# hijack_jtag_b.net
KiCad netlist of a schematic drawn in EAGLE
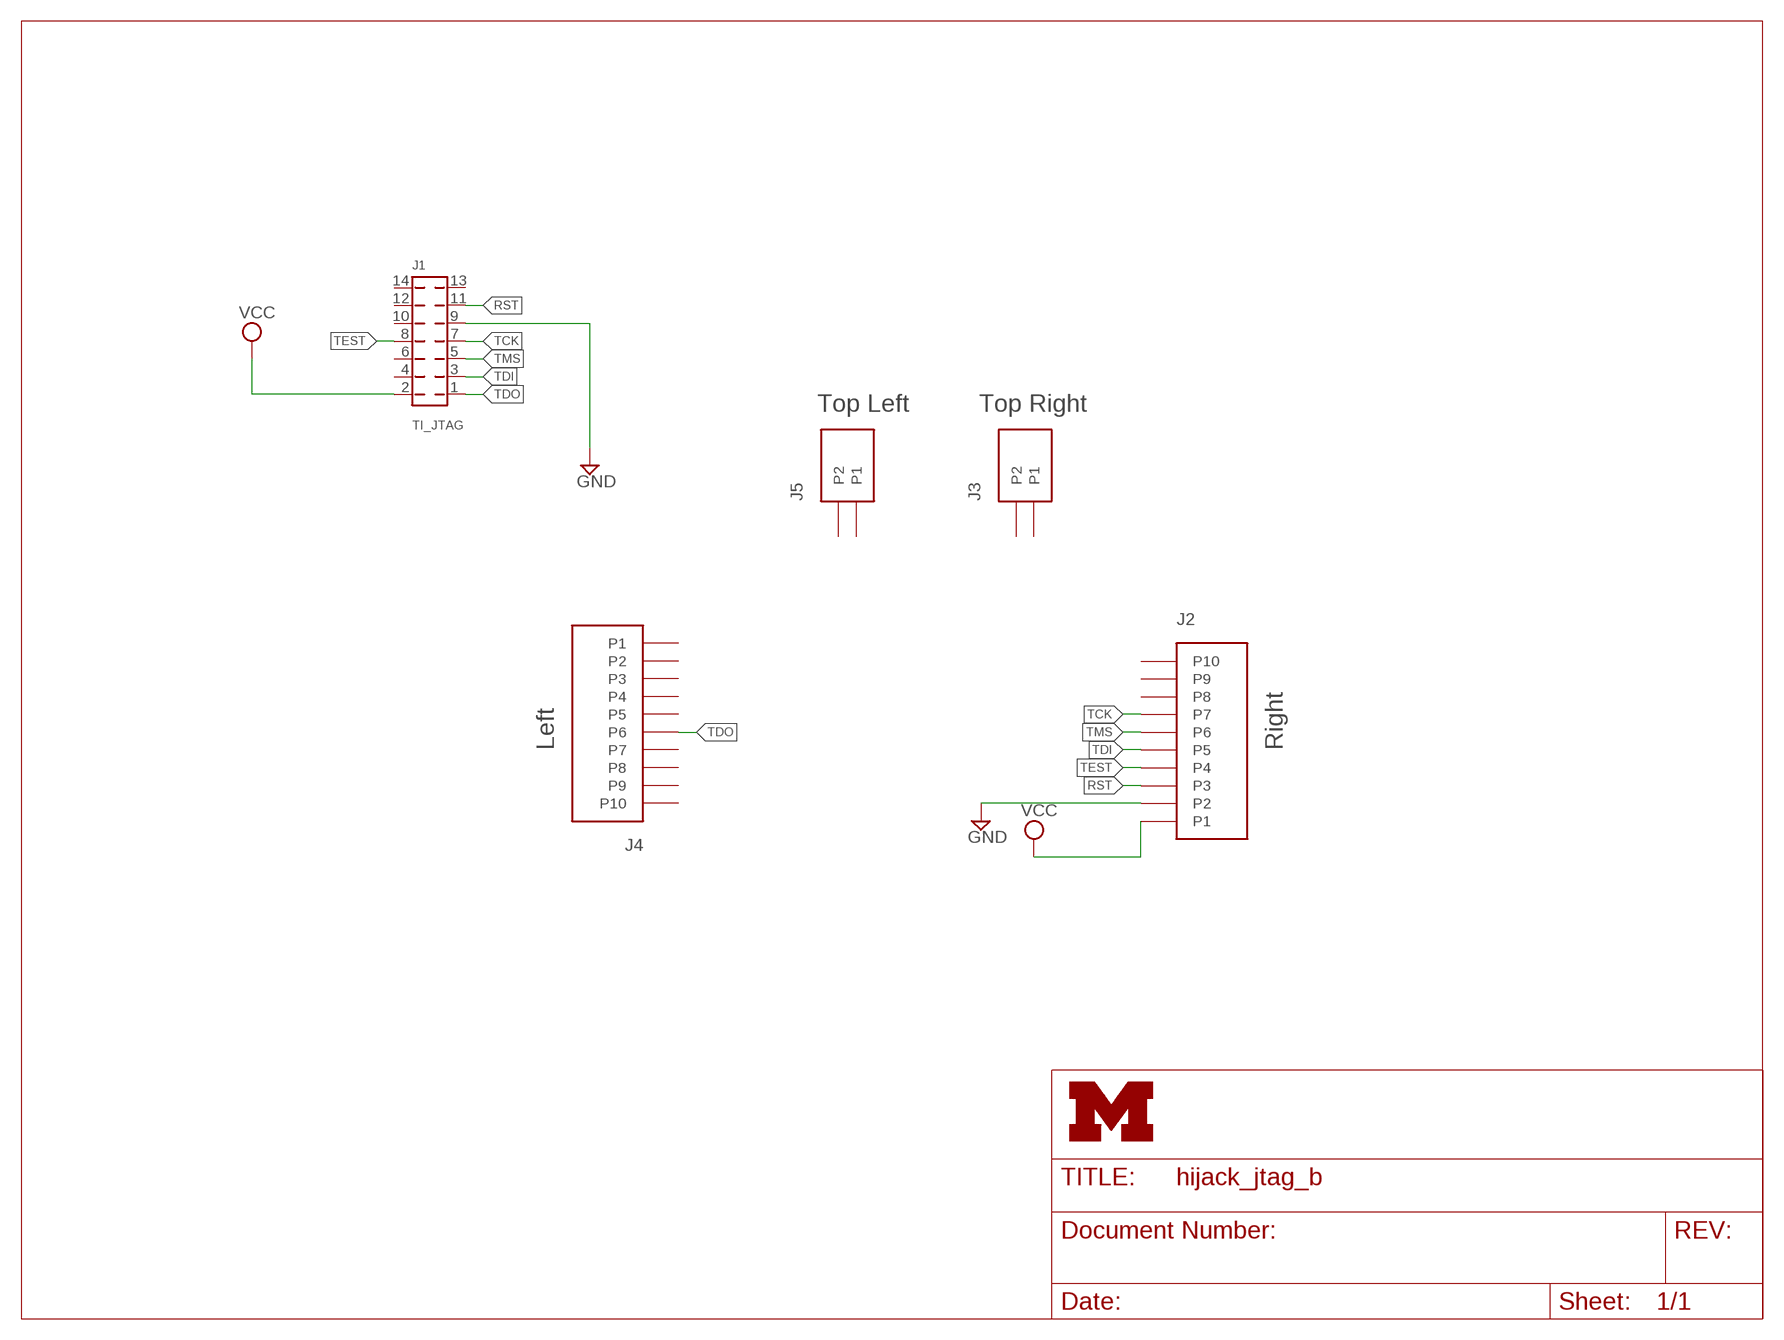
[diagram p0: schematic, sheet 1]

(export (version "E")
  (design (tool "Eeschema 10.0.6"))
  (components
    (comp (ref "J1")
      (value "TI_JTAG")
      (footprint "eagle-import:TST-107")
      (libsource (lib "eagle-import") (part "TI_JTAG"))
    )
    (comp (ref "J2")
      (value "HEADER10POS")
      (footprint "eagle-import:10PIN2MMHEADER")
      (libsource (lib "eagle-import") (part "HEADER10POS"))
    )
    (comp (ref "J3")
      (value "HEADER2POS")
      (footprint "eagle-import:2PIN2MMHEADER")
      (libsource (lib "eagle-import") (part "HEADER2POS"))
    )
    (comp (ref "J4")
      (value "HEADER10POS")
      (footprint "eagle-import:10PIN2MMHEADER")
      (libsource (lib "eagle-import") (part "HEADER10POS"))
    )
    (comp (ref "J5")
      (value "HEADER2POS")
      (footprint "eagle-import:2PIN2MMHEADER")
      (libsource (lib "eagle-import") (part "HEADER2POS"))
    )
    (comp (ref "U$2")
      (value "UMICH_SOLID")
      (footprint "eagle-import:UMICH_SOLID")
      (libsource (lib "eagle-import") (part "UMICH_SOLID"))
    )
  )
  (nets
    (net (code "1") (name "GND") (class "Default")
      (node (ref "J1") (pin "9") (pinfunction "P$9_9") (pintype "bidirectional"))
      (node (ref "J2") (pin "P2") (pinfunction "P2_P2") (pintype "bidirectional"))
    )
    (net (code "2") (name "RST") (class "Default")
      (node (ref "J1") (pin "11") (pinfunction "P$11_11") (pintype "bidirectional"))
      (node (ref "J2") (pin "P3") (pinfunction "P3_P3") (pintype "bidirectional"))
    )
    (net (code "3") (name "TCK") (class "Default")
      (node (ref "J1") (pin "7") (pinfunction "P$7_7") (pintype "bidirectional"))
      (node (ref "J2") (pin "P7") (pinfunction "P7_P7") (pintype "bidirectional"))
    )
    (net (code "4") (name "TDI") (class "Default")
      (node (ref "J1") (pin "3") (pinfunction "P$3_3") (pintype "bidirectional"))
      (node (ref "J2") (pin "P5") (pinfunction "P5_P5") (pintype "bidirectional"))
    )
    (net (code "5") (name "TDO") (class "Default")
      (node (ref "J1") (pin "1") (pinfunction "P$1_1") (pintype "bidirectional"))
      (node (ref "J4") (pin "P6") (pinfunction "P6_P6") (pintype "bidirectional"))
    )
    (net (code "6") (name "TEST") (class "Default")
      (node (ref "J1") (pin "8") (pinfunction "P$8_8") (pintype "bidirectional"))
      (node (ref "J2") (pin "P4") (pinfunction "P4_P4") (pintype "bidirectional"))
    )
    (net (code "7") (name "TMS") (class "Default")
      (node (ref "J1") (pin "5") (pinfunction "P$5_5") (pintype "bidirectional"))
      (node (ref "J2") (pin "P6") (pinfunction "P6_P6") (pintype "bidirectional"))
    )
    (net (code "8") (name "VCC") (class "Default")
      (node (ref "J1") (pin "2") (pinfunction "P$2_2") (pintype "bidirectional"))
      (node (ref "J2") (pin "P1") (pinfunction "P1_P1") (pintype "bidirectional"))
    )
    (net (code "9") (name "unconnected-(J1-P$4-Pad4)") (class "Default")
      (node (ref "J1") (pin "4") (pinfunction "P$4_4") (pintype "bidirectional"))
    )
    (net (code "10") (name "unconnected-(J1-P$6-Pad6)") (class "Default")
      (node (ref "J1") (pin "6") (pinfunction "P$6_6") (pintype "bidirectional"))
    )
    (net (code "11") (name "unconnected-(J1-P$10-Pad10)") (class "Default")
      (node (ref "J1") (pin "10") (pinfunction "P$10_10") (pintype "bidirectional"))
    )
    (net (code "12") (name "unconnected-(J1-P$12-Pad12)") (class "Default")
      (node (ref "J1") (pin "12") (pinfunction "P$12_12") (pintype "bidirectional"))
    )
    (net (code "13") (name "unconnected-(J1-P$13-Pad13)") (class "Default")
      (node (ref "J1") (pin "13") (pinfunction "P$13_13") (pintype "bidirectional"))
    )
    (net (code "14") (name "unconnected-(J1-P$14-Pad14)") (class "Default")
      (node (ref "J1") (pin "14") (pinfunction "P$14_14") (pintype "bidirectional"))
    )
    (net (code "15") (name "unconnected-(J2-PadP8)") (class "Default")
      (node (ref "J2") (pin "P8") (pinfunction "P8_P8") (pintype "bidirectional"))
    )
    (net (code "16") (name "unconnected-(J2-PadP9)") (class "Default")
      (node (ref "J2") (pin "P9") (pinfunction "P9_P9") (pintype "bidirectional"))
    )
    (net (code "17") (name "unconnected-(J2-PadP10)") (class "Default")
      (node (ref "J2") (pin "P10") (pinfunction "P10_P10") (pintype "bidirectional"))
    )
    (net (code "18") (name "unconnected-(J3-PadP1)") (class "Default")
      (node (ref "J3") (pin "P1") (pinfunction "P1_P1") (pintype "bidirectional"))
    )
    (net (code "19") (name "unconnected-(J3-PadP2)") (class "Default")
      (node (ref "J3") (pin "P2") (pinfunction "P2_P2") (pintype "bidirectional"))
    )
    (net (code "20") (name "unconnected-(J4-PadP1)") (class "Default")
      (node (ref "J4") (pin "P1") (pinfunction "P1_P1") (pintype "bidirectional"))
    )
    (net (code "21") (name "unconnected-(J4-PadP2)") (class "Default")
      (node (ref "J4") (pin "P2") (pinfunction "P2_P2") (pintype "bidirectional"))
    )
    (net (code "22") (name "unconnected-(J4-PadP3)") (class "Default")
      (node (ref "J4") (pin "P3") (pinfunction "P3_P3") (pintype "bidirectional"))
    )
    (net (code "23") (name "unconnected-(J4-PadP4)") (class "Default")
      (node (ref "J4") (pin "P4") (pinfunction "P4_P4") (pintype "bidirectional"))
    )
    (net (code "24") (name "unconnected-(J4-PadP5)") (class "Default")
      (node (ref "J4") (pin "P5") (pinfunction "P5_P5") (pintype "bidirectional"))
    )
    (net (code "25") (name "unconnected-(J4-PadP7)") (class "Default")
      (node (ref "J4") (pin "P7") (pinfunction "P7_P7") (pintype "bidirectional"))
    )
    (net (code "26") (name "unconnected-(J4-PadP8)") (class "Default")
      (node (ref "J4") (pin "P8") (pinfunction "P8_P8") (pintype "bidirectional"))
    )
    (net (code "27") (name "unconnected-(J4-PadP9)") (class "Default")
      (node (ref "J4") (pin "P9") (pinfunction "P9_P9") (pintype "bidirectional"))
    )
    (net (code "28") (name "unconnected-(J4-PadP10)") (class "Default")
      (node (ref "J4") (pin "P10") (pinfunction "P10_P10") (pintype "bidirectional"))
    )
    (net (code "29") (name "unconnected-(J5-PadP1)") (class "Default")
      (node (ref "J5") (pin "P1") (pinfunction "P1_P1") (pintype "bidirectional"))
    )
    (net (code "30") (name "unconnected-(J5-PadP2)") (class "Default")
      (node (ref "J5") (pin "P2") (pinfunction "P2_P2") (pintype "bidirectional"))
    )
  )
)
